# lpc.net
KiCad netlist of a schematic drawn in EAGLE
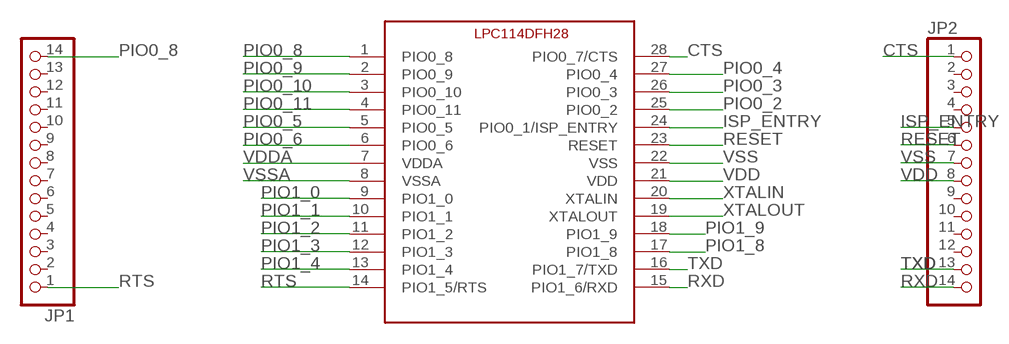
[diagram p0: schematic, sheet 1]

(export (version "E")
  (design (tool "Eeschema 10.0.6"))
  (components
    (comp (ref "JP1")
      (value "PINHD-1X14-CB")
      (footprint "eagle-import:1X14-CB")
      (libsource (lib "eagle-import") (part "PINHD-1X14-CB"))
    )
    (comp (ref "JP2")
      (value "PINHD-1X14-CB")
      (footprint "eagle-import:1X14-CB")
      (libsource (lib "eagle-import") (part "PINHD-1X14-CB"))
    )
    (comp (ref "U$1")
      (value "MUC-LPC1114")
      (footprint "eagle-import:MUC-LPC1114")
      (libsource (lib "eagle-import") (part "MUC-LPC1114"))
    )
  )
  (nets
    (net (code "1") (name "/CTS") (class "Default")
      (node (ref "JP2") (pin "1") (pinfunction "1_1") (pintype "passive"))
      (node (ref "U$1") (pin "28") (pinfunction "PIO0_7/CTS_28") (pintype "bidirectional"))
    )
    (net (code "2") (name "/ISP_ENTRY") (class "Default")
      (node (ref "JP2") (pin "5") (pinfunction "5_5") (pintype "passive"))
      (node (ref "U$1") (pin "24") (pinfunction "PIO0_1/ISP_ENTRY_24") (pintype "bidirectional"))
    )
    (net (code "3") (name "/PIO0_2") (class "Default")
      (node (ref "U$1") (pin "25") (pinfunction "PIO0_2_25") (pintype "bidirectional"))
    )
    (net (code "4") (name "/PIO0_3") (class "Default")
      (node (ref "U$1") (pin "26") (pinfunction "PIO0_3_26") (pintype "bidirectional"))
    )
    (net (code "5") (name "/PIO0_4") (class "Default")
      (node (ref "U$1") (pin "27") (pinfunction "PIO0_4_27") (pintype "bidirectional"))
    )
    (net (code "6") (name "/PIO0_5") (class "Default")
      (node (ref "U$1") (pin "5") (pinfunction "PIO0_5_5") (pintype "bidirectional"))
    )
    (net (code "7") (name "/PIO0_6") (class "Default")
      (node (ref "U$1") (pin "6") (pinfunction "PIO0_6_6") (pintype "bidirectional"))
    )
    (net (code "8") (name "/PIO0_8") (class "Default")
      (node (ref "JP1") (pin "14") (pinfunction "14_14") (pintype "passive"))
      (node (ref "U$1") (pin "1") (pinfunction "PIO0_8_1") (pintype "bidirectional"))
    )
    (net (code "9") (name "/PIO0_9") (class "Default")
      (node (ref "U$1") (pin "2") (pinfunction "PIO0_9_2") (pintype "bidirectional"))
    )
    (net (code "10") (name "/PIO0_10") (class "Default")
      (node (ref "U$1") (pin "3") (pinfunction "PIO0_10_3") (pintype "bidirectional"))
    )
    (net (code "11") (name "/PIO0_11") (class "Default")
      (node (ref "U$1") (pin "4") (pinfunction "PIO0_11_4") (pintype "bidirectional"))
    )
    (net (code "12") (name "/PIO1_0") (class "Default")
      (node (ref "U$1") (pin "9") (pinfunction "PIO1_0_9") (pintype "bidirectional"))
    )
    (net (code "13") (name "/PIO1_1") (class "Default")
      (node (ref "U$1") (pin "10") (pinfunction "PIO1_1_10") (pintype "bidirectional"))
    )
    (net (code "14") (name "/PIO1_2") (class "Default")
      (node (ref "U$1") (pin "11") (pinfunction "PIO1_2_11") (pintype "bidirectional"))
    )
    (net (code "15") (name "/PIO1_3") (class "Default")
      (node (ref "U$1") (pin "12") (pinfunction "PIO1_3_12") (pintype "bidirectional"))
    )
    (net (code "16") (name "/PIO1_4") (class "Default")
      (node (ref "U$1") (pin "13") (pinfunction "PIO1_4_13") (pintype "bidirectional"))
    )
    (net (code "17") (name "/PIO1_8") (class "Default")
      (node (ref "U$1") (pin "17") (pinfunction "PIO1_8_17") (pintype "bidirectional"))
    )
    (net (code "18") (name "/PIO1_9") (class "Default")
      (node (ref "U$1") (pin "18") (pinfunction "PIO1_9_18") (pintype "bidirectional"))
    )
    (net (code "19") (name "/RESET") (class "Default")
      (node (ref "JP2") (pin "6") (pinfunction "6_6") (pintype "passive"))
      (node (ref "U$1") (pin "23") (pinfunction "RESET_23") (pintype "bidirectional"))
    )
    (net (code "20") (name "/RTS") (class "Default")
      (node (ref "JP1") (pin "1") (pinfunction "1_1") (pintype "passive"))
      (node (ref "U$1") (pin "14") (pinfunction "PIO1_5/RTS_14") (pintype "bidirectional"))
    )
    (net (code "21") (name "/RXD") (class "Default")
      (node (ref "JP2") (pin "14") (pinfunction "14_14") (pintype "passive"))
      (node (ref "U$1") (pin "15") (pinfunction "PIO1_6/RXD_15") (pintype "bidirectional"))
    )
    (net (code "22") (name "/TXD") (class "Default")
      (node (ref "JP2") (pin "13") (pinfunction "13_13") (pintype "passive"))
      (node (ref "U$1") (pin "16") (pinfunction "PIO1_7/TXD_16") (pintype "bidirectional"))
    )
    (net (code "23") (name "/VDD") (class "Default")
      (node (ref "JP2") (pin "8") (pinfunction "8_8") (pintype "passive"))
      (node (ref "U$1") (pin "21") (pinfunction "VDD_21") (pintype "bidirectional"))
    )
    (net (code "24") (name "/VDDA") (class "Default")
      (node (ref "U$1") (pin "7") (pinfunction "VDDA_7") (pintype "bidirectional"))
    )
    (net (code "25") (name "/VSS") (class "Default")
      (node (ref "JP2") (pin "7") (pinfunction "7_7") (pintype "passive"))
      (node (ref "U$1") (pin "22") (pinfunction "VSS_22") (pintype "bidirectional"))
    )
    (net (code "26") (name "/VSSA") (class "Default")
      (node (ref "U$1") (pin "8") (pinfunction "VSSA_8") (pintype "bidirectional"))
    )
    (net (code "27") (name "/XTALIN") (class "Default")
      (node (ref "U$1") (pin "20") (pinfunction "XTALIN_20") (pintype "bidirectional"))
    )
    (net (code "28") (name "/XTALOUT") (class "Default")
      (node (ref "U$1") (pin "19") (pinfunction "XTALOUT_19") (pintype "bidirectional"))
    )
    (net (code "29") (name "unconnected-(JP1-Pad2)") (class "Default")
      (node (ref "JP1") (pin "2") (pinfunction "2_2") (pintype "passive"))
    )
    (net (code "30") (name "unconnected-(JP1-Pad3)") (class "Default")
      (node (ref "JP1") (pin "3") (pinfunction "3_3") (pintype "passive"))
    )
    (net (code "31") (name "unconnected-(JP1-Pad4)") (class "Default")
      (node (ref "JP1") (pin "4") (pinfunction "4_4") (pintype "passive"))
    )
    (net (code "32") (name "unconnected-(JP1-Pad5)") (class "Default")
      (node (ref "JP1") (pin "5") (pinfunction "5_5") (pintype "passive"))
    )
    (net (code "33") (name "unconnected-(JP1-Pad6)") (class "Default")
      (node (ref "JP1") (pin "6") (pinfunction "6_6") (pintype "passive"))
    )
    (net (code "34") (name "unconnected-(JP1-Pad7)") (class "Default")
      (node (ref "JP1") (pin "7") (pinfunction "7_7") (pintype "passive"))
    )
    (net (code "35") (name "unconnected-(JP1-Pad8)") (class "Default")
      (node (ref "JP1") (pin "8") (pinfunction "8_8") (pintype "passive"))
    )
    (net (code "36") (name "unconnected-(JP1-Pad9)") (class "Default")
      (node (ref "JP1") (pin "9") (pinfunction "9_9") (pintype "passive"))
    )
    (net (code "37") (name "unconnected-(JP1-Pad10)") (class "Default")
      (node (ref "JP1") (pin "10") (pinfunction "10_10") (pintype "passive"))
    )
    (net (code "38") (name "unconnected-(JP1-Pad11)") (class "Default")
      (node (ref "JP1") (pin "11") (pinfunction "11_11") (pintype "passive"))
    )
    (net (code "39") (name "unconnected-(JP1-Pad12)") (class "Default")
      (node (ref "JP1") (pin "12") (pinfunction "12_12") (pintype "passive"))
    )
    (net (code "40") (name "unconnected-(JP1-Pad13)") (class "Default")
      (node (ref "JP1") (pin "13") (pinfunction "13_13") (pintype "passive"))
    )
    (net (code "41") (name "unconnected-(JP2-Pad2)") (class "Default")
      (node (ref "JP2") (pin "2") (pinfunction "2_2") (pintype "passive"))
    )
    (net (code "42") (name "unconnected-(JP2-Pad3)") (class "Default")
      (node (ref "JP2") (pin "3") (pinfunction "3_3") (pintype "passive"))
    )
    (net (code "43") (name "unconnected-(JP2-Pad4)") (class "Default")
      (node (ref "JP2") (pin "4") (pinfunction "4_4") (pintype "passive"))
    )
    (net (code "44") (name "unconnected-(JP2-Pad9)") (class "Default")
      (node (ref "JP2") (pin "9") (pinfunction "9_9") (pintype "passive"))
    )
    (net (code "45") (name "unconnected-(JP2-Pad10)") (class "Default")
      (node (ref "JP2") (pin "10") (pinfunction "10_10") (pintype "passive"))
    )
    (net (code "46") (name "unconnected-(JP2-Pad11)") (class "Default")
      (node (ref "JP2") (pin "11") (pinfunction "11_11") (pintype "passive"))
    )
    (net (code "47") (name "unconnected-(JP2-Pad12)") (class "Default")
      (node (ref "JP2") (pin "12") (pinfunction "12_12") (pintype "passive"))
    )
  )
)
